# TiLDA_Mk2_LCD_Breakout_v0_1.net
KiCad netlist of a schematic drawn in EAGLE
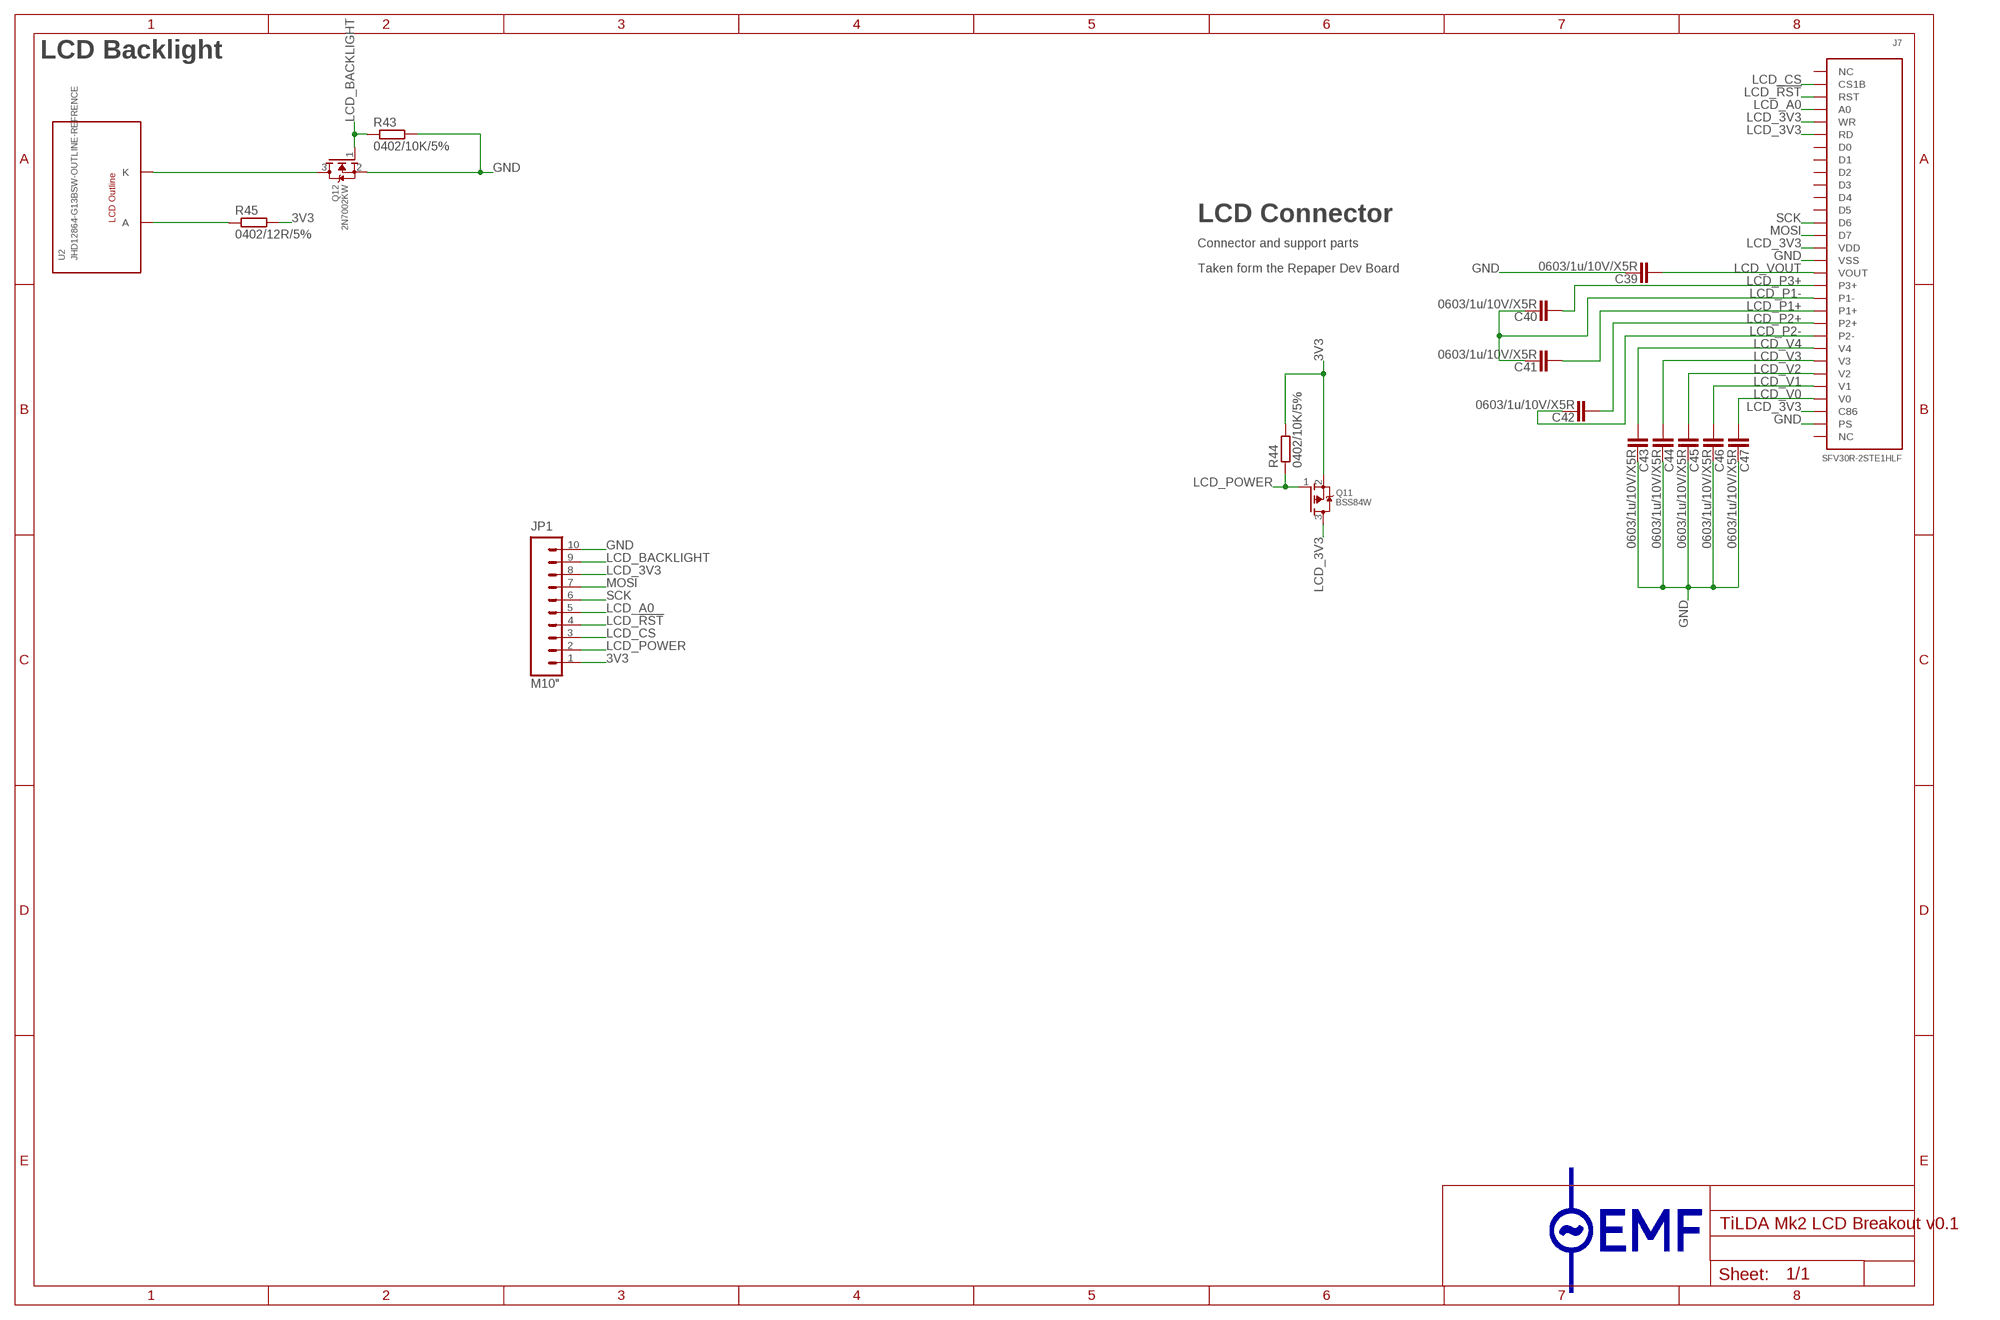
[diagram p0: schematic, sheet 1]

(export (version "E")
  (design (tool "Eeschema 10.0.6"))
  (components
    (comp (ref "C39")
      (value "0603/1u/10V/X5R")
      (footprint "eagle-import:C0603-ROUND")
      (libsource (lib "eagle-import") (part "C-EUC0603-ROUND"))
    )
    (comp (ref "C40")
      (value "0603/1u/10V/X5R")
      (footprint "eagle-import:C0603-ROUND")
      (libsource (lib "eagle-import") (part "C-EUC0603-ROUND"))
    )
    (comp (ref "C41")
      (value "0603/1u/10V/X5R")
      (footprint "eagle-import:C0603-ROUND")
      (libsource (lib "eagle-import") (part "C-EUC0603-ROUND"))
    )
    (comp (ref "C42")
      (value "0603/1u/10V/X5R")
      (footprint "eagle-import:C0603-ROUND")
      (libsource (lib "eagle-import") (part "C-EUC0603-ROUND"))
    )
    (comp (ref "C43")
      (value "0603/1u/10V/X5R")
      (footprint "eagle-import:C0603-ROUND")
      (libsource (lib "eagle-import") (part "C-EUC0603-ROUND"))
    )
    (comp (ref "C44")
      (value "0603/1u/10V/X5R")
      (footprint "eagle-import:C0603-ROUND")
      (libsource (lib "eagle-import") (part "C-EUC0603-ROUND"))
    )
    (comp (ref "C45")
      (value "0603/1u/10V/X5R")
      (footprint "eagle-import:C0603-ROUND")
      (libsource (lib "eagle-import") (part "C-EUC0603-ROUND"))
    )
    (comp (ref "C46")
      (value "0603/1u/10V/X5R")
      (footprint "eagle-import:C0603-ROUND")
      (libsource (lib "eagle-import") (part "C-EUC0603-ROUND"))
    )
    (comp (ref "C47")
      (value "0603/1u/10V/X5R")
      (footprint "eagle-import:C0603-ROUND")
      (libsource (lib "eagle-import") (part "C-EUC0603-ROUND"))
    )
    (comp (ref "J7")
      (value "SFV30R-2STE1HLF")
      (footprint "eagle-import:FPC30-WAY-BOTTOM")
      (libsource (lib "eagle-import") (part "JHD12863-G13BSW-CONNECTOR-30WAY-BOTTOM"))
    )
    (comp (ref "JP1")
      (value "M10\"")
      (footprint "eagle-import:1X10")
      (libsource (lib "eagle-import") (part "M10{dblquote}"))
    )
    (comp (ref "LOGO1")
      (value "EMFLOGO-SYMBOL")
      (footprint "eagle-import:EMFLOGO1")
      (libsource (lib "eagle-import") (part "EMFLOGO-SYMBOL"))
    )
    (comp (ref "Q11")
      (value "BSS84W")
      (footprint "eagle-import:SC70-3-R")
      (libsource (lib "eagle-import") (part "MOSFET-P-SC70-3"))
    )
    (comp (ref "Q12")
      (value "2N7002KW")
      (footprint "eagle-import:SC70-3-R")
      (libsource (lib "eagle-import") (part "MOSFET-NSC70-3"))
    )
    (comp (ref "R43")
      (value "0402/10K/5%")
      (footprint "eagle-import:R0402-ARDUINO-ROUND")
      (libsource (lib "eagle-import") (part "R-EU_R0402-ARDUINO-ROUND"))
    )
    (comp (ref "R44")
      (value "0402/10K/5%")
      (footprint "eagle-import:R0402-ARDUINO-ROUND")
      (libsource (lib "eagle-import") (part "R-EU_R0402-ARDUINO-ROUND"))
    )
    (comp (ref "R45")
      (value "0402/12R/5%")
      (footprint "eagle-import:R0402-ARDUINO-ROUND")
      (libsource (lib "eagle-import") (part "R-EU_R0402-ARDUINO-ROUND"))
    )
    (comp (ref "U2")
      (value "JHD12864-G13BSW-OUTLINE-REFRENCE")
      (footprint "eagle-import:JHD12864-G13BSW-OUTLINE-REF")
      (libsource (lib "eagle-import") (part "JHD12864-G13BSW-OUTLINE-REFRENCE"))
    )
  )
  (nets
    (net (code "1") (name "/3V3") (class "Default")
      (node (ref "JP1") (pin "1") (pinfunction "1_1") (pintype "passive"))
      (node (ref "Q11") (pin "2") (pinfunction "S_2") (pintype "bidirectional"))
      (node (ref "R44") (pin "2") (pinfunction "2_2") (pintype "passive"))
      (node (ref "R45") (pin "2") (pinfunction "2_2") (pintype "passive"))
    )
    (net (code "2") (name "/GND") (class "Default")
      (node (ref "C39") (pin "1") (pinfunction "1_1") (pintype "passive"))
      (node (ref "C43") (pin "1") (pinfunction "1_1") (pintype "passive"))
      (node (ref "C44") (pin "1") (pinfunction "1_1") (pintype "passive"))
      (node (ref "C45") (pin "1") (pinfunction "1_1") (pintype "passive"))
      (node (ref "C46") (pin "1") (pinfunction "1_1") (pintype "passive"))
      (node (ref "C47") (pin "1") (pinfunction "1_1") (pintype "passive"))
      (node (ref "J7") (pin "16") (pinfunction "VSS_16") (pintype "bidirectional"))
      (node (ref "J7") (pin "29") (pinfunction "PS_29") (pintype "bidirectional"))
      (node (ref "J7") (pin "M1") (pinfunction "VSS_M1") (pintype "bidirectional"))
      (node (ref "J7") (pin "M2") (pinfunction "VSS_M2") (pintype "bidirectional"))
      (node (ref "JP1") (pin "10") (pinfunction "10_10") (pintype "passive"))
      (node (ref "Q12") (pin "2") (pinfunction "S_2") (pintype "bidirectional"))
      (node (ref "R43") (pin "2") (pinfunction "2_2") (pintype "passive"))
    )
    (net (code "3") (name "/LCD_3V3") (class "Default")
      (node (ref "J7") (pin "15") (pinfunction "VDD_15") (pintype "bidirectional"))
      (node (ref "J7") (pin "28") (pinfunction "C86_28") (pintype "bidirectional"))
      (node (ref "J7") (pin "5") (pinfunction "WR_5") (pintype "bidirectional"))
      (node (ref "J7") (pin "6") (pinfunction "RD_6") (pintype "bidirectional"))
      (node (ref "JP1") (pin "8") (pinfunction "8_8") (pintype "passive"))
      (node (ref "Q11") (pin "3") (pinfunction "D_3") (pintype "bidirectional"))
    )
    (net (code "4") (name "/LCD_A0") (class "Default")
      (node (ref "J7") (pin "4") (pinfunction "A0_4") (pintype "bidirectional"))
      (node (ref "JP1") (pin "5") (pinfunction "5_5") (pintype "passive"))
    )
    (net (code "5") (name "/LCD_BACKLIGHT") (class "Default")
      (node (ref "JP1") (pin "9") (pinfunction "9_9") (pintype "passive"))
      (node (ref "Q12") (pin "1") (pinfunction "G_1") (pintype "bidirectional"))
      (node (ref "R43") (pin "1") (pinfunction "1_1") (pintype "passive"))
    )
    (net (code "6") (name "/LCD_CS") (class "Default")
      (node (ref "J7") (pin "2") (pinfunction "CS1B_2") (pintype "bidirectional"))
      (node (ref "JP1") (pin "3") (pinfunction "3_3") (pintype "passive"))
    )
    (net (code "7") (name "/LCD_P1+") (class "Default")
      (node (ref "C41") (pin "2") (pinfunction "2_2") (pintype "passive"))
      (node (ref "J7") (pin "20") (pinfunction "P1+_20") (pintype "bidirectional"))
    )
    (net (code "8") (name "/LCD_P1-") (class "Default")
      (node (ref "C40") (pin "1") (pinfunction "1_1") (pintype "passive"))
      (node (ref "C41") (pin "1") (pinfunction "1_1") (pintype "passive"))
      (node (ref "J7") (pin "19") (pinfunction "P1-_19") (pintype "bidirectional"))
    )
    (net (code "9") (name "/LCD_P2+") (class "Default")
      (node (ref "C42") (pin "2") (pinfunction "2_2") (pintype "passive"))
      (node (ref "J7") (pin "21") (pinfunction "P2+_21") (pintype "bidirectional"))
    )
    (net (code "10") (name "/LCD_P2-") (class "Default")
      (node (ref "C42") (pin "1") (pinfunction "1_1") (pintype "passive"))
      (node (ref "J7") (pin "22") (pinfunction "P2-_22") (pintype "bidirectional"))
    )
    (net (code "11") (name "/LCD_P3+") (class "Default")
      (node (ref "C40") (pin "2") (pinfunction "2_2") (pintype "passive"))
      (node (ref "J7") (pin "18") (pinfunction "P3+_18") (pintype "bidirectional"))
    )
    (net (code "12") (name "/LCD_POWER") (class "Default")
      (node (ref "JP1") (pin "2") (pinfunction "2_2") (pintype "passive"))
      (node (ref "Q11") (pin "1") (pinfunction "G_1") (pintype "bidirectional"))
      (node (ref "R44") (pin "1") (pinfunction "1_1") (pintype "passive"))
    )
    (net (code "13") (name "/LCD_V0") (class "Default")
      (node (ref "C47") (pin "2") (pinfunction "2_2") (pintype "passive"))
      (node (ref "J7") (pin "27") (pinfunction "V0_27") (pintype "bidirectional"))
    )
    (net (code "14") (name "/LCD_V1") (class "Default")
      (node (ref "C46") (pin "2") (pinfunction "2_2") (pintype "passive"))
      (node (ref "J7") (pin "26") (pinfunction "V1_26") (pintype "bidirectional"))
    )
    (net (code "15") (name "/LCD_V2") (class "Default")
      (node (ref "C45") (pin "2") (pinfunction "2_2") (pintype "passive"))
      (node (ref "J7") (pin "25") (pinfunction "V2_25") (pintype "bidirectional"))
    )
    (net (code "16") (name "/LCD_V3") (class "Default")
      (node (ref "C44") (pin "2") (pinfunction "2_2") (pintype "passive"))
      (node (ref "J7") (pin "24") (pinfunction "V3_24") (pintype "bidirectional"))
    )
    (net (code "17") (name "/LCD_V4") (class "Default")
      (node (ref "C43") (pin "2") (pinfunction "2_2") (pintype "passive"))
      (node (ref "J7") (pin "23") (pinfunction "V4_23") (pintype "bidirectional"))
    )
    (net (code "18") (name "/LCD_VOUT") (class "Default")
      (node (ref "C39") (pin "2") (pinfunction "2_2") (pintype "passive"))
      (node (ref "J7") (pin "17") (pinfunction "VOUT_17") (pintype "bidirectional"))
    )
    (net (code "19") (name "/LCD_~{RST}") (class "Default")
      (node (ref "J7") (pin "3") (pinfunction "RST_3") (pintype "bidirectional"))
      (node (ref "JP1") (pin "4") (pinfunction "4_4") (pintype "passive"))
    )
    (net (code "20") (name "/MOSI") (class "Default")
      (node (ref "J7") (pin "14") (pinfunction "D7_14") (pintype "bidirectional"))
      (node (ref "JP1") (pin "7") (pinfunction "7_7") (pintype "passive"))
    )
    (net (code "21") (name "/SCK") (class "Default")
      (node (ref "J7") (pin "13") (pinfunction "D6_13") (pintype "bidirectional"))
      (node (ref "JP1") (pin "6") (pinfunction "6_6") (pintype "passive"))
    )
    (net (code "22") (name "Net-(Q12-D)") (class "Default")
      (node (ref "Q12") (pin "3") (pinfunction "D_3") (pintype "bidirectional"))
      (node (ref "U2") (pin "K") (pinfunction "K_K") (pintype "bidirectional"))
    )
    (net (code "23") (name "Net-(R45-Pad1)") (class "Default")
      (node (ref "R45") (pin "1") (pinfunction "1_1") (pintype "passive"))
      (node (ref "U2") (pin "A") (pinfunction "A_A") (pintype "bidirectional"))
    )
    (net (code "24") (name "unconnected-(J7-D0-Pad7)") (class "Default")
      (node (ref "J7") (pin "7") (pinfunction "D0_7") (pintype "bidirectional"))
    )
    (net (code "25") (name "unconnected-(J7-D1-Pad8)") (class "Default")
      (node (ref "J7") (pin "8") (pinfunction "D1_8") (pintype "bidirectional"))
    )
    (net (code "26") (name "unconnected-(J7-D2-Pad9)") (class "Default")
      (node (ref "J7") (pin "9") (pinfunction "D2_9") (pintype "bidirectional"))
    )
    (net (code "27") (name "unconnected-(J7-D3-Pad10)") (class "Default")
      (node (ref "J7") (pin "10") (pinfunction "D3_10") (pintype "bidirectional"))
    )
    (net (code "28") (name "unconnected-(J7-D4-Pad11)") (class "Default")
      (node (ref "J7") (pin "11") (pinfunction "D4_11") (pintype "bidirectional"))
    )
    (net (code "29") (name "unconnected-(J7-D5-Pad12)") (class "Default")
      (node (ref "J7") (pin "12") (pinfunction "D5_12") (pintype "bidirectional"))
    )
    (net (code "30") (name "unconnected-(J7-NC-Pad1)") (class "Default")
      (node (ref "J7") (pin "1") (pinfunction "NC_1") (pintype "bidirectional"))
    )
    (net (code "31") (name "unconnected-(J7-NC-Pad30)") (class "Default")
      (node (ref "J7") (pin "30") (pinfunction "NC_30") (pintype "bidirectional"))
    )
  )
)
